# COMS0001_Beacon.net
KiCad netlist of a schematic drawn in Altium Designer
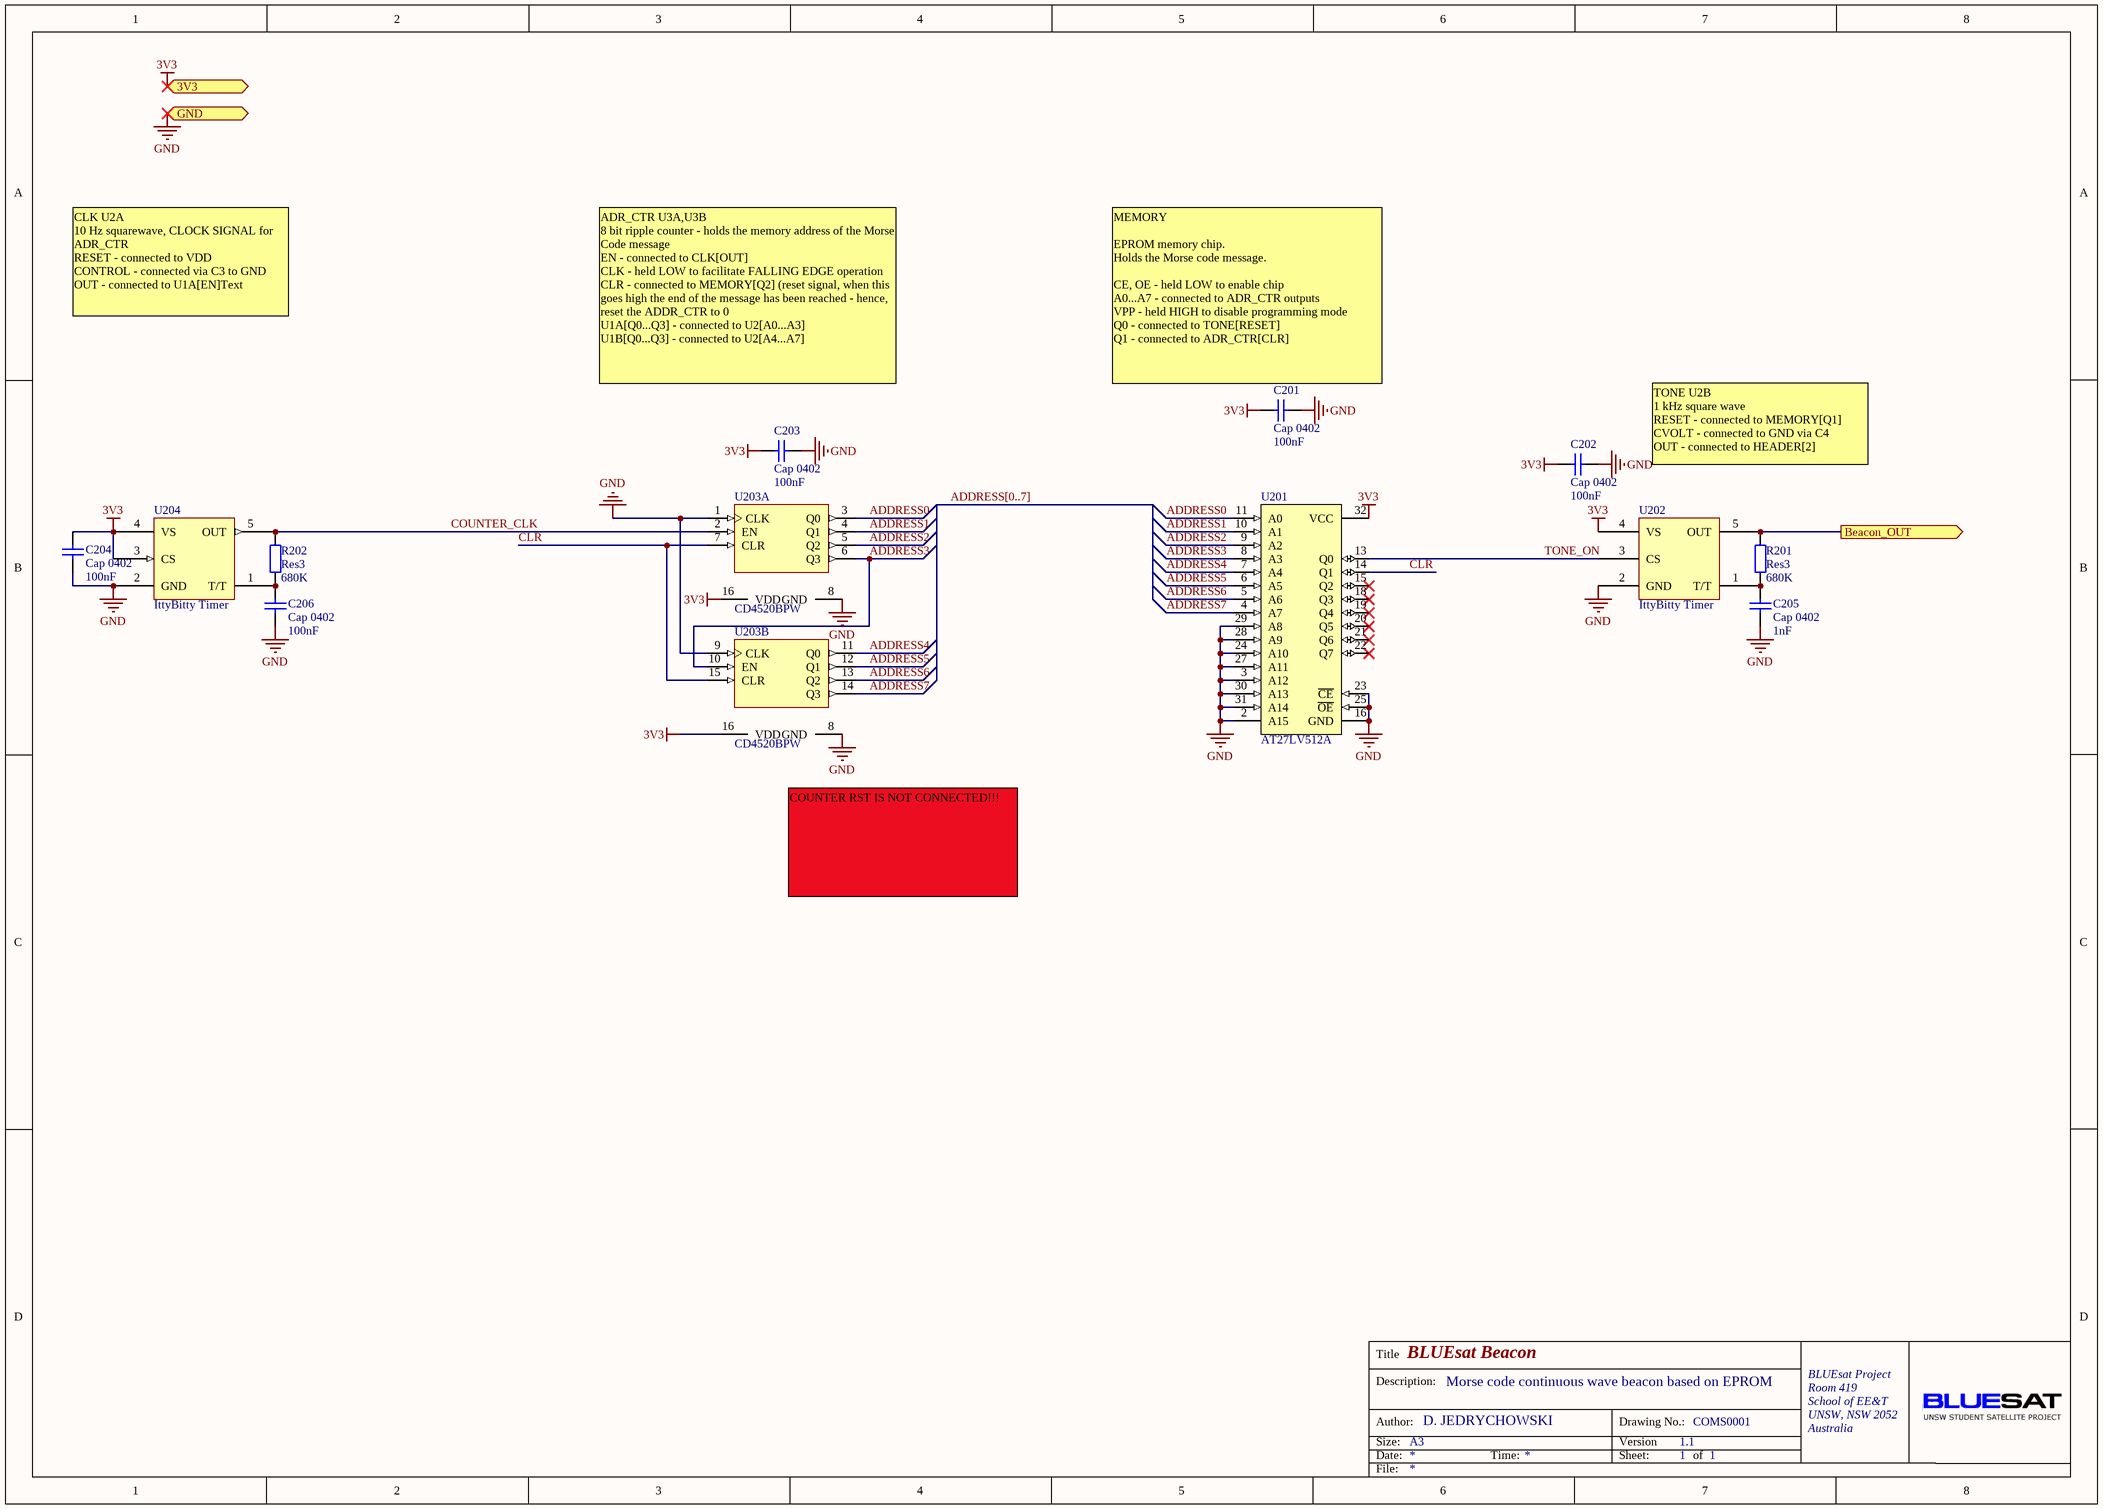
[diagram p0: COMS0001_Beacon.SchDoc]

(export (version "E")
  (design (tool "Eeschema 10.0.6"))
  (components
    (comp (ref "C201")
      (value "Cap 0402")
      (footprint "CAPC1005X06L")
      (description "Capacitor")
      (fields (field (name "ALTIUM_VALUE") "100nF") (field (name "PUBLISHER") "Altium Limited"))
      (libsource (lib "CSC") (part "Cap 0402"))
    )
    (comp (ref "C202")
      (value "Cap 0402")
      (footprint "CAPC1005X06L")
      (description "Capacitor")
      (fields (field (name "ALTIUM_VALUE") "100nF") (field (name "PUBLISHER") "Altium Limited"))
      (libsource (lib "CSC") (part "Cap 0402"))
    )
    (comp (ref "C203")
      (value "Cap 0402")
      (footprint "CAPC1005X06L")
      (description "Capacitor")
      (fields (field (name "ALTIUM_VALUE") "100nF") (field (name "PUBLISHER") "Altium Limited"))
      (libsource (lib "CSC") (part "Cap 0402"))
    )
    (comp (ref "C204")
      (value "Cap 0402")
      (footprint "CAPC1005X06L")
      (description "Capacitor")
      (fields (field (name "ALTIUM_VALUE") "100nF") (field (name "PUBLISHER") "Altium Limited"))
      (libsource (lib "CSC") (part "Cap 0402"))
    )
    (comp (ref "C205")
      (value "Cap 0402")
      (footprint "CAPC1005X06L")
      (description "Capacitor")
      (fields (field (name "ALTIUM_VALUE") "1nF") (field (name "PUBLISHER") "Altium Limited"))
      (libsource (lib "CSC") (part "Cap 0402"))
    )
    (comp (ref "C206")
      (value "Cap 0402")
      (footprint "CAPC1005X06L")
      (description "Capacitor")
      (fields (field (name "ALTIUM_VALUE") "100nF") (field (name "PUBLISHER") "Altium Limited"))
      (libsource (lib "CSC") (part "Cap 0402"))
    )
    (comp (ref "R201")
      (value "Res3")
      (footprint "RESC1005X06L")
      (description "Resistor")
      (fields (field (name "ALTIUM_VALUE") "680K") (field (name "PUBLISHER") "Altium Limited"))
      (libsource (lib "CSC") (part "Res3"))
    )
    (comp (ref "R202")
      (value "Res3")
      (footprint "RESC1005X06L")
      (description "Resistor")
      (fields (field (name "ALTIUM_VALUE") "680K") (field (name "PUBLISHER") "Altium Limited"))
      (libsource (lib "CSC") (part "Res3"))
    )
    (comp (ref "U201")
      (value "AT27LV512A")
      (footprint "Comms Board Small Footprints:PLCC7*9")
      (description "512 Kbit (32Kb X 8) UV EPROM and OTP EPROM")
      (fields (field (name "PUBLISHER") "Altium Limited"))
      (libsource (lib "Comms Board Small Footprints") (part "AT27LV512A"))
    )
    (comp (ref "U202")
      (value "IttyBitty Timer")
      (footprint "Comms Board Small Footprints:SOT23-5")
      (description "Miniature Astable Timer Chip")
      (libsource (lib "Comms Board Small Footprints") (part "MIC1557"))
    )
    (comp (ref "U203")
      (value "CD4520BPW")
      (footprint "TSSOP16")
      (description "Dual Binary Up-Counter")
      (libsource (lib "Comms Board Small Footprints") (part "CD4520BPW"))
    )
    (comp (ref "U204")
      (value "IttyBitty Timer")
      (footprint "Comms Board Small Footprints:SOT23-5")
      (description "Miniature Astable Timer Chip")
      (libsource (lib "Comms Board Small Footprints") (part "MIC1557"))
    )
  )
  (nets
    (net (code "1") (name "/ADDRESS0") (class "Default")
      (node (ref "U201") (pin "11") (pinfunction "A0_11") (pintype "input"))
      (node (ref "U203") (pin "3") (pinfunction "Q0_3") (pintype "output"))
    )
    (net (code "2") (name "/ADDRESS1") (class "Default")
      (node (ref "U201") (pin "10") (pinfunction "A1_10") (pintype "input"))
      (node (ref "U203") (pin "4") (pinfunction "Q1_4") (pintype "output"))
    )
    (net (code "3") (name "/ADDRESS2") (class "Default")
      (node (ref "U201") (pin "9") (pinfunction "A2_9") (pintype "input"))
      (node (ref "U203") (pin "5") (pinfunction "Q2_5") (pintype "output"))
    )
    (net (code "4") (name "/ADDRESS3") (class "Default")
      (node (ref "U201") (pin "8") (pinfunction "A3_8") (pintype "input"))
      (node (ref "U203") (pin "10") (pinfunction "EN_10") (pintype "input"))
      (node (ref "U203") (pin "6") (pinfunction "Q3_6") (pintype "output"))
    )
    (net (code "5") (name "/ADDRESS4") (class "Default")
      (node (ref "U201") (pin "7") (pinfunction "A4_7") (pintype "input"))
      (node (ref "U203") (pin "11") (pinfunction "Q0_11") (pintype "output"))
    )
    (net (code "6") (name "/ADDRESS5") (class "Default")
      (node (ref "U201") (pin "6") (pinfunction "A5_6") (pintype "input"))
      (node (ref "U203") (pin "12") (pinfunction "Q1_12") (pintype "output"))
    )
    (net (code "7") (name "/ADDRESS6") (class "Default")
      (node (ref "U201") (pin "5") (pinfunction "A6_5") (pintype "input"))
      (node (ref "U203") (pin "13") (pinfunction "Q2_13") (pintype "output"))
    )
    (net (code "8") (name "/ADDRESS7") (class "Default")
      (node (ref "U201") (pin "4") (pinfunction "A7_4") (pintype "input"))
      (node (ref "U203") (pin "14") (pinfunction "Q3_14") (pintype "output"))
    )
    (net (code "10") (name "/Beacon_OUT") (class "Default")
      (node (ref "R201") (pin "1") (pinfunction "1_1") (pintype "passive"))
      (node (ref "U202") (pin "5") (pinfunction "OUT_5") (pintype "passive"))
    )
    (net (code "11") (name "/CLR") (class "Default")
      (node (ref "U201") (pin "14") (pinfunction "Q1_14") (pintype "bidirectional"))
      (node (ref "U203") (pin "15") (pinfunction "CLR_15") (pintype "input"))
      (node (ref "U203") (pin "7") (pinfunction "CLR_7") (pintype "input"))
    )
    (net (code "12") (name "/COUNTER_CLK") (class "Default")
      (node (ref "R202") (pin "1") (pinfunction "1_1") (pintype "passive"))
      (node (ref "U203") (pin "2") (pinfunction "EN_2") (pintype "input"))
      (node (ref "U204") (pin "5") (pinfunction "OUT_5") (pintype "passive"))
    )
    (net (code "13") (name "/TONE_ON") (class "Default")
      (node (ref "U201") (pin "13") (pinfunction "Q0_13") (pintype "bidirectional"))
      (node (ref "U202") (pin "3") (pinfunction "CS_3") (pintype "passive"))
    )
    (net (code "14") (name "3V3") (class "Default")
      (node (ref "C201") (pin "1") (pinfunction "1_1") (pintype "passive"))
      (node (ref "C202") (pin "1") (pinfunction "1_1") (pintype "passive"))
      (node (ref "C203") (pin "1") (pinfunction "1_1") (pintype "passive"))
      (node (ref "C204") (pin "2") (pinfunction "2_2") (pintype "passive"))
      (node (ref "U201") (pin "32") (pinfunction "VCC_32") (pintype "power_in"))
      (node (ref "U202") (pin "4") (pinfunction "VS_4") (pintype "passive"))
      (node (ref "U203") (pin "16") (pinfunction "VDD_16") (pintype "power_in"))
      (node (ref "U204") (pin "3") (pinfunction "CS_3") (pintype "passive"))
      (node (ref "U204") (pin "4") (pinfunction "VS_4") (pintype "passive"))
    )
    (net (code "15") (name "GND") (class "Default")
      (node (ref "C201") (pin "2") (pinfunction "2_2") (pintype "passive"))
      (node (ref "C202") (pin "2") (pinfunction "2_2") (pintype "passive"))
      (node (ref "C203") (pin "2") (pinfunction "2_2") (pintype "passive"))
      (node (ref "C204") (pin "1") (pinfunction "1_1") (pintype "passive"))
      (node (ref "C205") (pin "1") (pinfunction "1_1") (pintype "passive"))
      (node (ref "C206") (pin "1") (pinfunction "1_1") (pintype "passive"))
      (node (ref "U201") (pin "16") (pinfunction "GND_16") (pintype "power_in"))
      (node (ref "U201") (pin "2") (pinfunction "A15_2") (pintype "passive"))
      (node (ref "U201") (pin "23") (pinfunction "~{CE}_23") (pintype "input"))
      (node (ref "U201") (pin "24") (pinfunction "A10_24") (pintype "input"))
      (node (ref "U201") (pin "25") (pinfunction "~{OE}_25") (pintype "input"))
      (node (ref "U201") (pin "27") (pinfunction "A11_27") (pintype "input"))
      (node (ref "U201") (pin "28") (pinfunction "A9_28") (pintype "input"))
      (node (ref "U201") (pin "29") (pinfunction "A8_29") (pintype "input"))
      (node (ref "U201") (pin "3") (pinfunction "A12_3") (pintype "input"))
      (node (ref "U201") (pin "30") (pinfunction "A13_30") (pintype "input"))
      (node (ref "U201") (pin "31") (pinfunction "A14_31") (pintype "input"))
      (node (ref "U202") (pin "2") (pinfunction "GND_2") (pintype "passive"))
      (node (ref "U203") (pin "1") (pinfunction "CLK_1") (pintype "input"))
      (node (ref "U203") (pin "8") (pinfunction "GND_8") (pintype "power_in"))
      (node (ref "U203") (pin "9") (pinfunction "CLK_9") (pintype "input"))
      (node (ref "U204") (pin "2") (pinfunction "GND_2") (pintype "passive"))
    )
    (net (code "16") (name "Net-(U202-T{slash}T)") (class "Default")
      (node (ref "C205") (pin "2") (pinfunction "2_2") (pintype "passive"))
      (node (ref "R201") (pin "2") (pinfunction "2_2") (pintype "passive"))
      (node (ref "U202") (pin "1") (pinfunction "T/T_1") (pintype "passive"))
    )
    (net (code "17") (name "Net-(U204-T{slash}T)") (class "Default")
      (node (ref "C206") (pin "2") (pinfunction "2_2") (pintype "passive"))
      (node (ref "R202") (pin "2") (pinfunction "2_2") (pintype "passive"))
      (node (ref "U204") (pin "1") (pinfunction "T/T_1") (pintype "passive"))
    )
    (net (code "18") (name "unconnected-(U201-Q2-Pad15)") (class "Default")
      (node (ref "U201") (pin "15") (pinfunction "Q2_15") (pintype "bidirectional+no_connect"))
    )
    (net (code "19") (name "unconnected-(U201-Q3-Pad18)") (class "Default")
      (node (ref "U201") (pin "18") (pinfunction "Q3_18") (pintype "bidirectional+no_connect"))
    )
    (net (code "20") (name "unconnected-(U201-Q4-Pad19)") (class "Default")
      (node (ref "U201") (pin "19") (pinfunction "Q4_19") (pintype "bidirectional+no_connect"))
    )
    (net (code "21") (name "unconnected-(U201-Q5-Pad20)") (class "Default")
      (node (ref "U201") (pin "20") (pinfunction "Q5_20") (pintype "bidirectional+no_connect"))
    )
    (net (code "22") (name "unconnected-(U201-Q6-Pad21)") (class "Default")
      (node (ref "U201") (pin "21") (pinfunction "Q6_21") (pintype "bidirectional+no_connect"))
    )
    (net (code "23") (name "unconnected-(U201-Q7-Pad22)") (class "Default")
      (node (ref "U201") (pin "22") (pinfunction "Q7_22") (pintype "bidirectional+no_connect"))
    )
  )
)
